# MasterDMX.net
KiCad netlist of a schematic drawn in Altium Designer
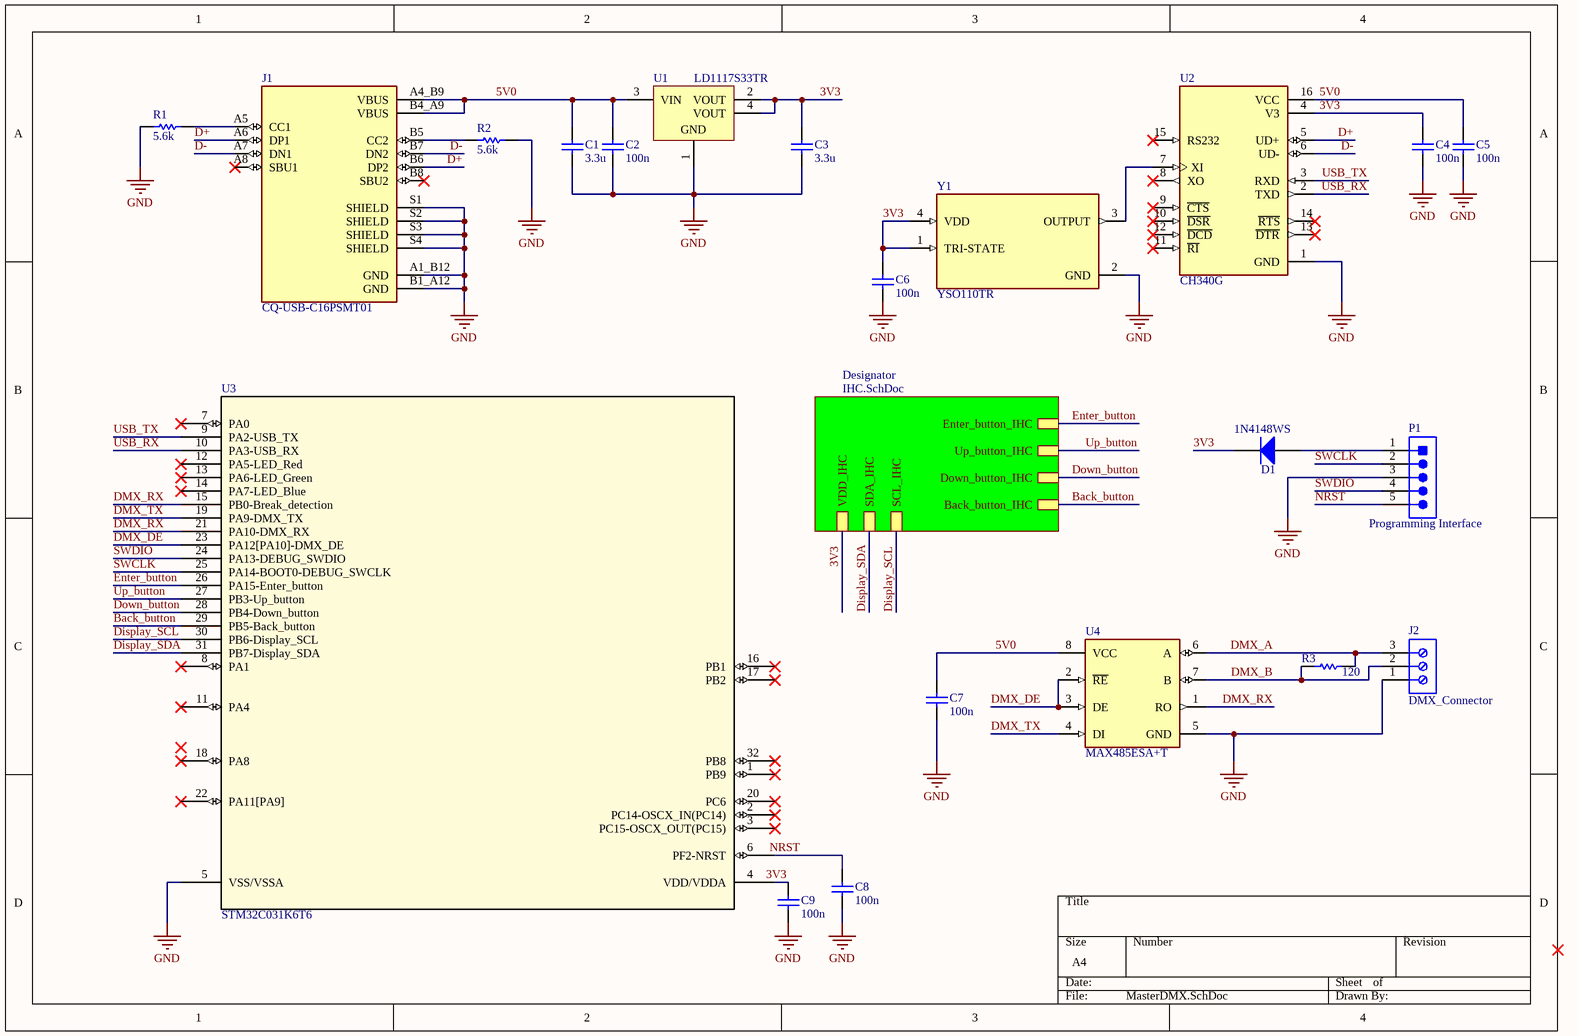
[diagram p0: MasterDMX.SchDoc]

(export (version "E")
  (design (tool "Eeschema 10.0.6"))
  (components
    (comp (ref "C1")
      (value "3.3u")
      (footprint "C2012[0805]")
      (description "Capacitor")
      (libsource (lib "Basic Library") (part "C"))
    )
    (comp (ref "C2")
      (value "100n")
      (footprint "C3216[1206]")
      (description "Capacitor")
      (libsource (lib "Basic Library") (part "C"))
    )
    (comp (ref "C3")
      (value "3.3u")
      (footprint "C2012[0805]")
      (description "Capacitor")
      (libsource (lib "Basic Library") (part "C"))
    )
    (comp (ref "C4")
      (value "100n")
      (footprint "C3216[1206]")
      (description "Capacitor")
      (libsource (lib "Basic Library") (part "C"))
    )
    (comp (ref "C5")
      (value "100n")
      (footprint "C3216[1206]")
      (description "Capacitor")
      (libsource (lib "Basic Library") (part "C"))
    )
    (comp (ref "C6")
      (value "100n")
      (footprint "C3216[1206]")
      (description "Capacitor")
      (libsource (lib "Basic Library") (part "C"))
    )
    (comp (ref "C7")
      (value "100n")
      (footprint "C3216[1206]")
      (description "Capacitor")
      (libsource (lib "Basic Library") (part "C"))
    )
    (comp (ref "C8")
      (value "100n")
      (footprint "C3216[1206]")
      (description "Capacitor")
      (libsource (lib "Basic Library") (part "C"))
    )
    (comp (ref "C9")
      (value "100n")
      (footprint "C3216[1206]")
      (description "Capacitor")
      (libsource (lib "Basic Library") (part "C"))
    )
    (comp (ref "D1")
      (value "1N4148WS")
      (footprint "FAIR-SOD-323_V")
      (description "Small Signal Diode, 75 V, 0.15 A, -55 to 150 degC, 2-Pin SOD-323, RoHS, Tape and Reel")
      (fields (field (name "MANUFACTURER") "Fairchild"))
      (libsource (lib "Guilherme Silveira") (part "D-AK-2"))
    )
    (comp (ref "J1")
      (value "CQ-USB-C16PSMT01")
      (footprint "SHENZHEN-CHUANGQIN-TECHNOLOGY_CQ-USB-C16PSMT01")
      (description "C Type USB Type-C Female Plug 16 Pin Connector Power Charger Jack Port")
      (fields (field (name "MF") "Shenzen Chuangqin Technology"))
      (libsource (lib "CQ-USB-C16PSMT01") (part "CQ-USB-C16PSMT01"))
    )
    (comp (ref "J2")
      (value "DMX_Connector")
      (footprint "691214110003")
      (fields (field (name "VOLTAGE") "300V"))
      (libsource (lib "Altium Content Vault") (part "TBL - 1R - 03P - Screw"))
    )
    (comp (ref "P1")
      (value "Programming Interface")
      (footprint "FCI-77311-5_V")
      (fields (field (name "MANUFACTURER") "FCI Electronics"))
      (libsource (lib "Guilherme Silveira") (part "CN-1P-M-R5"))
    )
    (comp (ref "R1")
      (value "5.6k")
      (footprint "R2012[0805]")
      (description "Resistor")
      (libsource (lib "Basic Library") (part "R"))
    )
    (comp (ref "R2")
      (value "5.6k")
      (footprint "R2012[0805]")
      (description "Resistor")
      (libsource (lib "Basic Library") (part "R"))
    )
    (comp (ref "R3")
      (value "120")
      (footprint "R2012[0805]")
      (description "Resistor")
      (libsource (lib "Basic Library") (part "R"))
    )
    (comp (ref "U1")
      (value "LD1117S33TR")
      (footprint "STM-SOT-223_M")
      (fields (field (name "POWER") "12W") (field (name "MANUFACTURER") "STMicroelectronics"))
      (libsource (lib "Guilherme Silveira") (part "STM-LD1117-SOT223-4"))
    )
    (comp (ref "U2")
      (value "CH340G")
      (footprint "SOIC127P600X180-16N")
      (description "USB Interface Integrated Circuit")
      (fields (field (name "MP") "Ch340G") (field (name "MF") "WCH"))
      (libsource (lib "CH340G") (part "CH340G"))
    )
    (comp (ref "U3")
      (value "STM32C031K6T6")
      (footprint "LQFP32_7X7_STM")
      (description "No Description Available")
      (libsource (lib "STM32C031K6T6") (part "STM32C031K6T6"))
    )
    (comp (ref "U4")
      (value "MAX485ESA+T")
      (footprint "FP-S8-2-MFG")
      (description "Line Transceiver, 1 Func, 1 Driver, 1 Rcvr, CMOS, PDSO8")
      (libsource (lib "Guilherme Silveira") (part "5a32c1deac0ec46b72dd39c04a7e29b"))
    )
    (comp (ref "Y1")
      (value "YSO110TR")
      (footprint "OSC_ECS-TXO-2016-33-120-TR")
      (fields (field (name "MP") "ECS-TXO-2016-33-120-TR"))
      (libsource (lib "Guilherme Silveira") (part "ECS-TXO-2016-33-120-TR"))
    )
  )
  (nets
    (net (code "1") (name "/3V3") (class "Default")
      (node (ref "C3") (pin "2") (pinfunction "2_2") (pintype "passive"))
      (node (ref "C4") (pin "2") (pinfunction "2_2") (pintype "passive"))
      (node (ref "C6") (pin "2") (pinfunction "2_2") (pintype "passive"))
      (node (ref "C9") (pin "2") (pinfunction "2_2") (pintype "passive"))
      (node (ref "D1") (pin "2") (pinfunction "K_2") (pintype "passive"))
      (node (ref "U1") (pin "2") (pinfunction "VOUT_2") (pintype "power_in"))
      (node (ref "U1") (pin "4") (pinfunction "VOUT_4") (pintype "power_in"))
      (node (ref "U2") (pin "4") (pinfunction "V3_4") (pintype "power_in"))
      (node (ref "U3") (pin "4") (pinfunction "VDD/VDDA_4") (pintype "power_in"))
      (node (ref "Y1") (pin "1") (pinfunction "TRI-STATE_1") (pintype "input"))
      (node (ref "Y1") (pin "4") (pinfunction "VDD_4") (pintype "input"))
    )
    (net (code "2") (name "/5V0") (class "Default")
      (node (ref "C1") (pin "2") (pinfunction "2_2") (pintype "passive"))
      (node (ref "C2") (pin "2") (pinfunction "2_2") (pintype "passive"))
      (node (ref "C5") (pin "2") (pinfunction "2_2") (pintype "passive"))
      (node (ref "C7") (pin "2") (pinfunction "2_2") (pintype "passive"))
      (node (ref "J1") (pin "A4_B9") (pinfunction "VBUS_A4_B9") (pintype "power_in"))
      (node (ref "J1") (pin "B4_A9") (pinfunction "VBUS_B4_A9") (pintype "power_in"))
      (node (ref "U1") (pin "3") (pinfunction "VIN_3") (pintype "power_in"))
      (node (ref "U2") (pin "16") (pinfunction "VCC_16") (pintype "power_in"))
      (node (ref "U4") (pin "8") (pinfunction "VCC_8") (pintype "power_in"))
    )
    (net (code "3") (name "/Back_button") (class "Default")
      (node (ref "U3") (pin "29") (pinfunction "PB5-Back_button_29") (pintype "passive"))
    )
    (net (code "4") (name "/D+") (class "Default")
      (node (ref "J1") (pin "A6") (pinfunction "DP1_A6") (pintype "bidirectional"))
      (node (ref "J1") (pin "B6") (pinfunction "DP2_B6") (pintype "bidirectional"))
      (node (ref "U2") (pin "5") (pinfunction "UD+_5") (pintype "bidirectional"))
    )
    (net (code "5") (name "/D-") (class "Default")
      (node (ref "J1") (pin "A7") (pinfunction "DN1_A7") (pintype "bidirectional"))
      (node (ref "J1") (pin "B7") (pinfunction "DN2_B7") (pintype "bidirectional"))
      (node (ref "U2") (pin "6") (pinfunction "UD-_6") (pintype "bidirectional"))
    )
    (net (code "6") (name "/DMX_A") (class "Default")
      (node (ref "J2") (pin "3") (pinfunction "1_3") (pintype "passive"))
      (node (ref "R3") (pin "1") (pinfunction "1_1") (pintype "passive"))
      (node (ref "U4") (pin "6") (pinfunction "A_6") (pintype "bidirectional"))
    )
    (net (code "7") (name "/DMX_B") (class "Default")
      (node (ref "J2") (pin "2") (pinfunction "2_2") (pintype "passive"))
      (node (ref "R3") (pin "2") (pinfunction "2_2") (pintype "passive"))
      (node (ref "U4") (pin "7") (pinfunction "B_7") (pintype "bidirectional"))
    )
    (net (code "8") (name "/DMX_DE") (class "Default")
      (node (ref "U3") (pin "23") (pinfunction "PA12[PA10]-DMX_DE_23") (pintype "passive"))
      (node (ref "U4") (pin "2") (pinfunction "~{RE}_2") (pintype "input"))
      (node (ref "U4") (pin "3") (pinfunction "DE_3") (pintype "input"))
    )
    (net (code "9") (name "/DMX_RX") (class "Default")
      (node (ref "U3") (pin "15") (pinfunction "PB0-Break_detection_15") (pintype "passive"))
      (node (ref "U3") (pin "21") (pinfunction "PA10-DMX_RX_21") (pintype "passive"))
      (node (ref "U4") (pin "1") (pinfunction "RO_1") (pintype "output"))
    )
    (net (code "10") (name "/DMX_TX") (class "Default")
      (node (ref "U3") (pin "19") (pinfunction "PA9-DMX_TX_19") (pintype "passive"))
      (node (ref "U4") (pin "4") (pinfunction "DI_4") (pintype "input"))
    )
    (net (code "11") (name "/Display_SCL") (class "Default")
      (node (ref "U3") (pin "30") (pinfunction "PB6-Display_SCL_30") (pintype "passive"))
    )
    (net (code "12") (name "/Display_SDA") (class "Default")
      (node (ref "U3") (pin "31") (pinfunction "PB7-Display_SDA_31") (pintype "passive"))
    )
    (net (code "13") (name "/Down_button") (class "Default")
      (node (ref "U3") (pin "28") (pinfunction "PB4-Down_button_28") (pintype "passive"))
    )
    (net (code "14") (name "/Enter_button") (class "Default")
      (node (ref "U3") (pin "26") (pinfunction "PA15-Enter_button_26") (pintype "passive"))
    )
    (net (code "15") (name "/NRST") (class "Default")
      (node (ref "C8") (pin "2") (pinfunction "2_2") (pintype "passive"))
      (node (ref "P1") (pin "5") (pinfunction "CTS_5") (pintype "passive"))
      (node (ref "U3") (pin "6") (pinfunction "PF2-NRST_6") (pintype "bidirectional"))
    )
    (net (code "16") (name "/SWCLK") (class "Default")
      (node (ref "P1") (pin "2") (pinfunction "RXI_2") (pintype "passive"))
      (node (ref "U3") (pin "25") (pinfunction "PA14-BOOT0-DEBUG_SWCLK_25") (pintype "passive"))
    )
    (net (code "17") (name "/SWDIO") (class "Default")
      (node (ref "P1") (pin "4") (pinfunction "VCC_4") (pintype "passive"))
      (node (ref "U3") (pin "24") (pinfunction "PA13-DEBUG_SWDIO_24") (pintype "passive"))
    )
    (net (code "18") (name "/USB_RX") (class "Default")
      (node (ref "U2") (pin "2") (pinfunction "TXD_2") (pintype "output"))
      (node (ref "U3") (pin "10") (pinfunction "PA3-USB_RX_10") (pintype "passive"))
    )
    (net (code "19") (name "/USB_TX") (class "Default")
      (node (ref "U2") (pin "3") (pinfunction "RXD_3") (pintype "input"))
      (node (ref "U3") (pin "9") (pinfunction "PA2-USB_TX_9") (pintype "passive"))
    )
    (net (code "20") (name "/Up_button") (class "Default")
      (node (ref "U3") (pin "27") (pinfunction "PB3-Up_button_27") (pintype "passive"))
    )
    (net (code "21") (name "GND") (class "Default")
      (node (ref "C1") (pin "1") (pinfunction "1_1") (pintype "passive"))
      (node (ref "C2") (pin "1") (pinfunction "1_1") (pintype "passive"))
      (node (ref "C3") (pin "1") (pinfunction "1_1") (pintype "passive"))
      (node (ref "C4") (pin "1") (pinfunction "1_1") (pintype "passive"))
      (node (ref "C5") (pin "1") (pinfunction "1_1") (pintype "passive"))
      (node (ref "C6") (pin "1") (pinfunction "1_1") (pintype "passive"))
      (node (ref "C7") (pin "1") (pinfunction "1_1") (pintype "passive"))
      (node (ref "C8") (pin "1") (pinfunction "1_1") (pintype "passive"))
      (node (ref "C9") (pin "1") (pinfunction "1_1") (pintype "passive"))
      (node (ref "J1") (pin "A1_B12") (pinfunction "GND_A1_B12") (pintype "power_in"))
      (node (ref "J1") (pin "B1_A12") (pinfunction "GND_B1_A12") (pintype "power_in"))
      (node (ref "J1") (pin "S1") (pinfunction "SHIELD_S1") (pintype "passive"))
      (node (ref "J1") (pin "S2") (pinfunction "SHIELD_S2") (pintype "passive"))
      (node (ref "J1") (pin "S3") (pinfunction "SHIELD_S3") (pintype "passive"))
      (node (ref "J1") (pin "S4") (pinfunction "SHIELD_S4") (pintype "passive"))
      (node (ref "J2") (pin "1") (pinfunction "3_1") (pintype "passive"))
      (node (ref "P1") (pin "3") (pinfunction "TXO_3") (pintype "passive"))
      (node (ref "R1") (pin "1") (pinfunction "1_1") (pintype "passive"))
      (node (ref "R2") (pin "2") (pinfunction "2_2") (pintype "passive"))
      (node (ref "U1") (pin "1") (pinfunction "GND_1") (pintype "power_in"))
      (node (ref "U2") (pin "1") (pinfunction "GND_1") (pintype "power_in"))
      (node (ref "U3") (pin "5") (pinfunction "VSS/VSSA_5") (pintype "power_in"))
      (node (ref "U4") (pin "5") (pinfunction "GND_5") (pintype "power_in"))
      (node (ref "Y1") (pin "2") (pinfunction "GND_2") (pintype "power_in"))
    )
    (net (code "22") (name "Net-(D1-A)") (class "Default")
      (node (ref "D1") (pin "1") (pinfunction "A_1") (pintype "passive"))
      (node (ref "P1") (pin "1") (pinfunction "DTR_1") (pintype "passive"))
    )
    (net (code "23") (name "Net-(J1-CC1)") (class "Default")
      (node (ref "J1") (pin "A5") (pinfunction "CC1_A5") (pintype "bidirectional"))
      (node (ref "R1") (pin "2") (pinfunction "2_2") (pintype "passive"))
    )
    (net (code "24") (name "Net-(J1-CC2)") (class "Default")
      (node (ref "J1") (pin "B5") (pinfunction "CC2_B5") (pintype "bidirectional"))
      (node (ref "R2") (pin "1") (pinfunction "1_1") (pintype "passive"))
    )
    (net (code "25") (name "Net-(U2-XI)") (class "Default")
      (node (ref "U2") (pin "7") (pinfunction "XI_7") (pintype "input"))
      (node (ref "Y1") (pin "3") (pinfunction "OUTPUT_3") (pintype "output"))
    )
    (net (code "26") (name "unconnected-(J1-SBU1-PadA8)") (class "Default")
      (node (ref "J1") (pin "A8") (pinfunction "SBU1_A8") (pintype "bidirectional+no_connect"))
    )
    (net (code "27") (name "unconnected-(J1-SBU2-PadB8)") (class "Default")
      (node (ref "J1") (pin "B8") (pinfunction "SBU2_B8") (pintype "bidirectional+no_connect"))
    )
    (net (code "28") (name "unconnected-(U2-RS232-Pad15)") (class "Default")
      (node (ref "U2") (pin "15") (pinfunction "RS232_15") (pintype "input+no_connect"))
    )
    (net (code "29") (name "unconnected-(U2-XO-Pad8)") (class "Default")
      (node (ref "U2") (pin "8") (pinfunction "XO_8") (pintype "output+no_connect"))
    )
    (net (code "30") (name "unconnected-(U2-~{CTS}-Pad9)") (class "Default")
      (node (ref "U2") (pin "9") (pinfunction "~{CTS}_9") (pintype "input+no_connect"))
    )
    (net (code "31") (name "unconnected-(U2-~{DCD}-Pad12)") (class "Default")
      (node (ref "U2") (pin "12") (pinfunction "~{DCD}_12") (pintype "input+no_connect"))
    )
    (net (code "32") (name "unconnected-(U2-~{DSR}-Pad10)") (class "Default")
      (node (ref "U2") (pin "10") (pinfunction "~{DSR}_10") (pintype "input+no_connect"))
    )
    (net (code "33") (name "unconnected-(U2-~{DTR}-Pad13)") (class "Default")
      (node (ref "U2") (pin "13") (pinfunction "~{DTR}_13") (pintype "output+no_connect"))
    )
    (net (code "34") (name "unconnected-(U2-~{RI}-Pad11)") (class "Default")
      (node (ref "U2") (pin "11") (pinfunction "~{RI}_11") (pintype "input+no_connect"))
    )
    (net (code "35") (name "unconnected-(U2-~{RTS}-Pad14)") (class "Default")
      (node (ref "U2") (pin "14") (pinfunction "~{RTS}_14") (pintype "output+no_connect"))
    )
    (net (code "36") (name "unconnected-(U3-PA0-Pad7)") (class "Default")
      (node (ref "U3") (pin "7") (pinfunction "PA0_7") (pintype "bidirectional+no_connect"))
    )
    (net (code "37") (name "unconnected-(U3-PA1-Pad8)") (class "Default")
      (node (ref "U3") (pin "8") (pinfunction "PA1_8") (pintype "bidirectional+no_connect"))
    )
    (net (code "38") (name "unconnected-(U3-PA4-Pad11)") (class "Default")
      (node (ref "U3") (pin "11") (pinfunction "PA4_11") (pintype "bidirectional+no_connect"))
    )
    (net (code "39") (name "unconnected-(U3-PA5-LED_Red-Pad12)") (class "Default")
      (node (ref "U3") (pin "12") (pinfunction "PA5-LED_Red_12") (pintype "passive+no_connect"))
    )
    (net (code "40") (name "unconnected-(U3-PA6-LED_Green-Pad13)") (class "Default")
      (node (ref "U3") (pin "13") (pinfunction "PA6-LED_Green_13") (pintype "passive+no_connect"))
    )
    (net (code "41") (name "unconnected-(U3-PA7-LED_Blue-Pad14)") (class "Default")
      (node (ref "U3") (pin "14") (pinfunction "PA7-LED_Blue_14") (pintype "passive+no_connect"))
    )
    (net (code "42") (name "unconnected-(U3-PA8-Pad18)") (class "Default")
      (node (ref "U3") (pin "18") (pinfunction "PA8_18") (pintype "bidirectional+no_connect"))
    )
    (net (code "43") (name "unconnected-(U3-PA11[PA9]-Pad22)") (class "Default")
      (node (ref "U3") (pin "22") (pinfunction "PA11[PA9]_22") (pintype "bidirectional+no_connect"))
    )
    (net (code "44") (name "unconnected-(U3-PB1-Pad16)") (class "Default")
      (node (ref "U3") (pin "16") (pinfunction "PB1_16") (pintype "bidirectional+no_connect"))
    )
    (net (code "45") (name "unconnected-(U3-PB2-Pad17)") (class "Default")
      (node (ref "U3") (pin "17") (pinfunction "PB2_17") (pintype "bidirectional+no_connect"))
    )
    (net (code "46") (name "unconnected-(U3-PB8-Pad32)") (class "Default")
      (node (ref "U3") (pin "32") (pinfunction "PB8_32") (pintype "bidirectional+no_connect"))
    )
    (net (code "47") (name "unconnected-(U3-PB9-Pad1)") (class "Default")
      (node (ref "U3") (pin "1") (pinfunction "PB9_1") (pintype "bidirectional+no_connect"))
    )
    (net (code "48") (name "unconnected-(U3-PC6-Pad20)") (class "Default")
      (node (ref "U3") (pin "20") (pinfunction "PC6_20") (pintype "bidirectional+no_connect"))
    )
    (net (code "49") (name "unconnected-(U3-PC14-OSCX_IN(PC14)-Pad2)") (class "Default")
      (node (ref "U3") (pin "2") (pinfunction "PC14-OSCX_IN(PC14)_2") (pintype "bidirectional+no_connect"))
    )
    (net (code "50") (name "unconnected-(U3-PC15-OSCX_OUT(PC15)-Pad3)") (class "Default")
      (node (ref "U3") (pin "3") (pinfunction "PC15-OSCX_OUT(PC15)_3") (pintype "bidirectional+no_connect"))
    )
  )
)
